# Power.net
KiCad netlist of a schematic drawn in Altium Designer
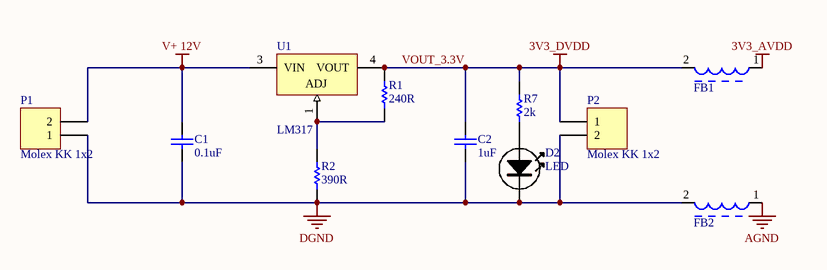
[diagram p0: Power.SchDoc]

(export (version "E")
  (design (tool "Eeschema 10.0.6"))
  (components
    (comp (ref "C1")
      (value "0.1uF")
      (footprint "C0805")
      (description "0805 Capacitor")
      (libsource (lib "PARSEC") (part "C0805"))
    )
    (comp (ref "C2")
      (value "1uF")
      (footprint "C0805")
      (description "0805 Capacitor")
      (libsource (lib "PARSEC") (part "C0805"))
    )
    (comp (ref "D2")
      (value "LED")
      (footprint "0805LED")
      (fields
        (field (name "MANUFACTURER") "OSRAM Opto Semiconductors Inc")
        (field (name "MANUFACTURER PART NUMBER") "LS T676-Q1R2-1-Z")
      )
      (libsource (lib "PARSEC") (part "LED"))
    )
    (comp (ref "FB1")
      (value "FERRITE")
      (footprint "R0805")
      (description "FERRITE BEAD 0805")
      (libsource (lib "PARSEC") (part "FERRITE"))
    )
    (comp (ref "FB2")
      (value "FERRITE")
      (footprint "R0805")
      (description "FERRITE BEAD 0805")
      (libsource (lib "PARSEC") (part "FERRITE"))
    )
    (comp (ref "P1")
      (value "Molex KK 1x2")
      (footprint "Molex KK 2x1")
      (description "1x2 Molex KK Connector")
      (libsource (lib "PARSEC") (part "Molex KK 1x2"))
    )
    (comp (ref "P2")
      (value "Molex KK 1x2")
      (footprint "Molex KK 2x1")
      (description "1x2 Molex KK Connector")
      (libsource (lib "") (part "Molex KK 1x2_1"))
    )
    (comp (ref "R1")
      (value "240R")
      (footprint "R0805")
      (description "RESISTOR 0805")
      (libsource (lib "PARSEC") (part "R0805"))
    )
    (comp (ref "R2")
      (value "390R")
      (footprint "R0805")
      (description "RESISTOR 0805")
      (libsource (lib "PARSEC") (part "R0805"))
    )
    (comp (ref "R7")
      (value "2k")
      (footprint "R0805")
      (description "RESISTOR 0805")
      (libsource (lib "PARSEC") (part "R0805"))
    )
    (comp (ref "U1")
      (value "LM317")
      (footprint "D-PAK")
      (description "Linear Voltage Regulator")
      (libsource (lib "PARSEC") (part "LM317"))
    )
  )
  (nets
    (net (code "1") (name "3V3_AVDD") (class "Default")
      (node (ref "FB1") (pin "1") (pinfunction "1_1") (pintype "passive"))
    )
    (net (code "2") (name "3V3_DVDD") (class "Default")
      (node (ref "C2") (pin "1") (pinfunction "1_1") (pintype "passive"))
      (node (ref "FB1") (pin "2") (pinfunction "2_2") (pintype "passive"))
      (node (ref "P2") (pin "1") (pinfunction "1_1") (pintype "passive"))
      (node (ref "R1") (pin "2") (pinfunction "2_2") (pintype "passive"))
      (node (ref "R7") (pin "2") (pinfunction "2_2") (pintype "passive"))
      (node (ref "U1") (pin "4") (pinfunction "VOUT_4") (pintype "power_in"))
    )
    (net (code "3") (name "AGND") (class "Default")
      (node (ref "FB2") (pin "1") (pinfunction "1_1") (pintype "passive"))
    )
    (net (code "4") (name "DGND") (class "Default")
      (node (ref "C1") (pin "2") (pinfunction "2_2") (pintype "passive"))
      (node (ref "C2") (pin "2") (pinfunction "2_2") (pintype "passive"))
      (node (ref "D2") (pin "K") (pintype "passive"))
      (node (ref "FB2") (pin "2") (pinfunction "2_2") (pintype "passive"))
      (node (ref "P1") (pin "1") (pinfunction "1_1") (pintype "passive"))
      (node (ref "P2") (pin "2") (pinfunction "2_2") (pintype "passive"))
      (node (ref "R2") (pin "1") (pinfunction "1_1") (pintype "passive"))
    )
    (net (code "5") (name "Net-(D2-PadA)") (class "Default")
      (node (ref "D2") (pin "A") (pintype "passive"))
      (node (ref "R7") (pin "1") (pinfunction "1_1") (pintype "passive"))
    )
    (net (code "6") (name "Net-(U1-ADJ)") (class "Default")
      (node (ref "R1") (pin "1") (pinfunction "1_1") (pintype "passive"))
      (node (ref "R2") (pin "2") (pinfunction "2_2") (pintype "passive"))
      (node (ref "U1") (pin "1") (pinfunction "ADJ_1") (pintype "input"))
    )
    (net (code "7") (name "V+ 12V") (class "Default")
      (node (ref "C1") (pin "1") (pinfunction "1_1") (pintype "passive"))
      (node (ref "P1") (pin "2") (pinfunction "2_2") (pintype "passive"))
      (node (ref "U1") (pin "3") (pinfunction "VIN_3") (pintype "power_in"))
    )
  )
)
